# SATA_Ports.net
KiCad netlist of a schematic drawn in Altium Designer
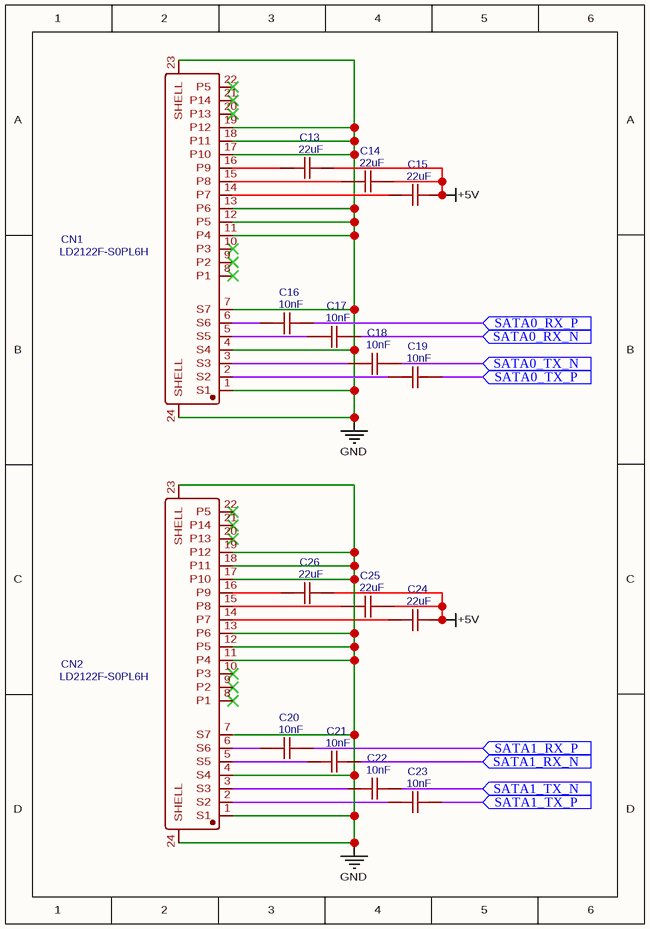
[diagram p0: SATA Ports.schdoc]

(export (version "E")
  (design (tool "Eeschema 10.0.6"))
  (components
    (comp (ref "C13")
      (value "22uF")
      (fields
        (field (name "MANUFACTURER") "Chinocera(华瓷)")
        (field (name "MANUFACTURER PART") "HGC0603R5226M160NTHJ")
        (field (name "CONTRIBUTOR") "lcsc")
      )
      (libsource (lib "altium-import") (part "root_0_22uF_"))
    )
    (comp (ref "C14")
      (value "22uF")
      (fields
        (field (name "MANUFACTURER") "Chinocera(华瓷)")
        (field (name "MANUFACTURER PART") "HGC0603R5226M160NTHJ")
        (field (name "CONTRIBUTOR") "lcsc")
      )
      (libsource (lib "altium-import") (part "root_0_22uF_"))
    )
    (comp (ref "C15")
      (value "22uF")
      (fields
        (field (name "MANUFACTURER") "Chinocera(华瓷)")
        (field (name "MANUFACTURER PART") "HGC0603R5226M160NTHJ")
        (field (name "CONTRIBUTOR") "lcsc")
      )
      (libsource (lib "altium-import") (part "root_0_22uF_"))
    )
    (comp (ref "C16")
      (value "10nF")
      (fields
        (field (name "MANUFACTURER") "FOJAN(富捷)")
        (field (name "MANUFACTURER PART") "FCC0402B103K500AT")
        (field (name "CONTRIBUTOR") "lcsc")
      )
      (libsource (lib "altium-import") (part "root_0_10nF_"))
    )
    (comp (ref "C17")
      (value "10nF")
      (fields
        (field (name "MANUFACTURER") "FOJAN(富捷)")
        (field (name "MANUFACTURER PART") "FCC0402B103K500AT")
        (field (name "CONTRIBUTOR") "lcsc")
      )
      (libsource (lib "altium-import") (part "root_0_10nF_"))
    )
    (comp (ref "C18")
      (value "10nF")
      (fields
        (field (name "MANUFACTURER") "FOJAN(富捷)")
        (field (name "MANUFACTURER PART") "FCC0402B103K500AT")
        (field (name "CONTRIBUTOR") "lcsc")
      )
      (libsource (lib "altium-import") (part "root_0_10nF_"))
    )
    (comp (ref "C19")
      (value "10nF")
      (fields
        (field (name "MANUFACTURER") "FOJAN(富捷)")
        (field (name "MANUFACTURER PART") "FCC0402B103K500AT")
        (field (name "CONTRIBUTOR") "lcsc")
      )
      (libsource (lib "altium-import") (part "root_0_10nF_"))
    )
    (comp (ref "C20")
      (value "10nF")
      (fields
        (field (name "MANUFACTURER") "FOJAN(富捷)")
        (field (name "MANUFACTURER PART") "FCC0402B103K500AT")
        (field (name "CONTRIBUTOR") "lcsc")
      )
      (libsource (lib "altium-import") (part "root_0_10nF_"))
    )
    (comp (ref "C21")
      (value "10nF")
      (fields
        (field (name "MANUFACTURER") "FOJAN(富捷)")
        (field (name "MANUFACTURER PART") "FCC0402B103K500AT")
        (field (name "CONTRIBUTOR") "lcsc")
      )
      (libsource (lib "altium-import") (part "root_0_10nF_"))
    )
    (comp (ref "C22")
      (value "10nF")
      (fields
        (field (name "MANUFACTURER") "FOJAN(富捷)")
        (field (name "MANUFACTURER PART") "FCC0402B103K500AT")
        (field (name "CONTRIBUTOR") "lcsc")
      )
      (libsource (lib "altium-import") (part "root_0_10nF_"))
    )
    (comp (ref "C23")
      (value "10nF")
      (fields
        (field (name "MANUFACTURER") "FOJAN(富捷)")
        (field (name "MANUFACTURER PART") "FCC0402B103K500AT")
        (field (name "CONTRIBUTOR") "lcsc")
      )
      (libsource (lib "altium-import") (part "root_0_10nF_"))
    )
    (comp (ref "C24")
      (value "22uF")
      (fields
        (field (name "MANUFACTURER") "Chinocera(华瓷)")
        (field (name "MANUFACTURER PART") "HGC0603R5226M160NTHJ")
        (field (name "CONTRIBUTOR") "lcsc")
      )
      (libsource (lib "altium-import") (part "root_0_22uF_"))
    )
    (comp (ref "C25")
      (value "22uF")
      (fields
        (field (name "MANUFACTURER") "Chinocera(华瓷)")
        (field (name "MANUFACTURER PART") "HGC0603R5226M160NTHJ")
        (field (name "CONTRIBUTOR") "lcsc")
      )
      (libsource (lib "altium-import") (part "root_0_22uF_"))
    )
    (comp (ref "C26")
      (value "22uF")
      (fields
        (field (name "MANUFACTURER") "Chinocera(华瓷)")
        (field (name "MANUFACTURER PART") "HGC0603R5226M160NTHJ")
        (field (name "CONTRIBUTOR") "lcsc")
      )
      (libsource (lib "altium-import") (part "root_0_22uF_"))
    )
    (comp (ref "CN1")
      (value "LD2122F-S0PL6H")
      (fields (field (name "MANUFACTURER") "FOXCONN(富士康)") (field (name "CONTRIBUTOR") "LCSC"))
      (libsource (lib "altium-import") (part "root_2_LD2122F-S0PL6H_"))
    )
    (comp (ref "CN2")
      (value "LD2122F-S0PL6H")
      (fields (field (name "MANUFACTURER") "FOXCONN(富士康)") (field (name "CONTRIBUTOR") "LCSC"))
      (libsource (lib "altium-import") (part "root_2_LD2122F-S0PL6H_"))
    )
  )
  (nets
    (net (code "1") (name "+5V") (class "Default")
      (node (ref "C13") (pin "2") (pinfunction "2_2") (pintype "passive"))
      (node (ref "C14") (pin "2") (pinfunction "2_2") (pintype "passive"))
      (node (ref "C15") (pin "2") (pinfunction "2_2") (pintype "passive"))
      (node (ref "C24") (pin "2") (pinfunction "2_2") (pintype "passive"))
      (node (ref "C25") (pin "2") (pinfunction "2_2") (pintype "passive"))
      (node (ref "C26") (pin "2") (pinfunction "2_2") (pintype "passive"))
    )
    (net (code "2") (name "/SATA0_RX_N") (class "Default")
      (node (ref "C17") (pin "2") (pinfunction "2_2") (pintype "passive"))
    )
    (net (code "3") (name "/SATA0_RX_P") (class "Default")
      (node (ref "C16") (pin "2") (pinfunction "2_2") (pintype "passive"))
    )
    (net (code "4") (name "/SATA0_TX_N") (class "Default")
      (node (ref "C18") (pin "2") (pinfunction "2_2") (pintype "passive"))
    )
    (net (code "5") (name "/SATA0_TX_P") (class "Default")
      (node (ref "C19") (pin "2") (pinfunction "2_2") (pintype "passive"))
    )
    (net (code "6") (name "/SATA1_RX_N") (class "Default")
      (node (ref "C21") (pin "2") (pinfunction "2_2") (pintype "passive"))
    )
    (net (code "7") (name "/SATA1_RX_P") (class "Default")
      (node (ref "C20") (pin "2") (pinfunction "2_2") (pintype "passive"))
    )
    (net (code "8") (name "/SATA1_TX_N") (class "Default")
      (node (ref "C22") (pin "2") (pinfunction "2_2") (pintype "passive"))
    )
    (net (code "9") (name "/SATA1_TX_P") (class "Default")
      (node (ref "C23") (pin "2") (pinfunction "2_2") (pintype "passive"))
    )
    (net (code "10") (name "GND") (class "Default")
      (node (ref "CN1") (pin "1") (pinfunction "S1_1") (pintype "passive"))
      (node (ref "CN1") (pin "11") (pinfunction "P4_11") (pintype "passive"))
      (node (ref "CN1") (pin "12") (pinfunction "P5_12") (pintype "passive"))
      (node (ref "CN1") (pin "13") (pinfunction "P6_13") (pintype "passive"))
      (node (ref "CN1") (pin "17") (pinfunction "P10_17") (pintype "passive"))
      (node (ref "CN1") (pin "18") (pinfunction "P11_18") (pintype "passive"))
      (node (ref "CN1") (pin "19") (pinfunction "P12_19") (pintype "passive"))
      (node (ref "CN1") (pin "23") (pinfunction "SHELL_23") (pintype "passive"))
      (node (ref "CN1") (pin "24") (pinfunction "SHELL_24") (pintype "passive"))
      (node (ref "CN1") (pin "4") (pinfunction "S4_4") (pintype "passive"))
      (node (ref "CN1") (pin "7") (pinfunction "S7_7") (pintype "passive"))
      (node (ref "CN2") (pin "1") (pinfunction "S1_1") (pintype "passive"))
      (node (ref "CN2") (pin "11") (pinfunction "P4_11") (pintype "passive"))
      (node (ref "CN2") (pin "12") (pinfunction "P5_12") (pintype "passive"))
      (node (ref "CN2") (pin "13") (pinfunction "P6_13") (pintype "passive"))
      (node (ref "CN2") (pin "17") (pinfunction "P10_17") (pintype "passive"))
      (node (ref "CN2") (pin "18") (pinfunction "P11_18") (pintype "passive"))
      (node (ref "CN2") (pin "19") (pinfunction "P12_19") (pintype "passive"))
      (node (ref "CN2") (pin "23") (pinfunction "SHELL_23") (pintype "passive"))
      (node (ref "CN2") (pin "24") (pinfunction "SHELL_24") (pintype "passive"))
      (node (ref "CN2") (pin "4") (pinfunction "S4_4") (pintype "passive"))
      (node (ref "CN2") (pin "7") (pinfunction "S7_7") (pintype "passive"))
    )
    (net (code "11") (name "Net-(CN1-P7)") (class "Default")
      (node (ref "C15") (pin "1") (pinfunction "1_1") (pintype "passive"))
      (node (ref "CN1") (pin "14") (pinfunction "P7_14") (pintype "passive"))
    )
    (net (code "12") (name "Net-(CN1-P8)") (class "Default")
      (node (ref "C14") (pin "1") (pinfunction "1_1") (pintype "passive"))
      (node (ref "CN1") (pin "15") (pinfunction "P8_15") (pintype "passive"))
    )
    (net (code "13") (name "Net-(CN1-P9)") (class "Default")
      (node (ref "C13") (pin "1") (pinfunction "1_1") (pintype "passive"))
      (node (ref "CN1") (pin "16") (pinfunction "P9_16") (pintype "passive"))
    )
    (net (code "14") (name "Net-(CN1-S2)") (class "Default")
      (node (ref "C19") (pin "1") (pinfunction "1_1") (pintype "passive"))
      (node (ref "CN1") (pin "2") (pinfunction "S2_2") (pintype "passive"))
    )
    (net (code "15") (name "Net-(CN1-S3)") (class "Default")
      (node (ref "C18") (pin "1") (pinfunction "1_1") (pintype "passive"))
      (node (ref "CN1") (pin "3") (pinfunction "S3_3") (pintype "passive"))
    )
    (net (code "16") (name "Net-(CN1-S5)") (class "Default")
      (node (ref "C17") (pin "1") (pinfunction "1_1") (pintype "passive"))
      (node (ref "CN1") (pin "5") (pinfunction "S5_5") (pintype "passive"))
    )
    (net (code "17") (name "Net-(CN1-S6)") (class "Default")
      (node (ref "C16") (pin "1") (pinfunction "1_1") (pintype "passive"))
      (node (ref "CN1") (pin "6") (pinfunction "S6_6") (pintype "passive"))
    )
    (net (code "18") (name "Net-(CN2-P7)") (class "Default")
      (node (ref "C24") (pin "1") (pinfunction "1_1") (pintype "passive"))
      (node (ref "CN2") (pin "14") (pinfunction "P7_14") (pintype "passive"))
    )
    (net (code "19") (name "Net-(CN2-P8)") (class "Default")
      (node (ref "C25") (pin "1") (pinfunction "1_1") (pintype "passive"))
      (node (ref "CN2") (pin "15") (pinfunction "P8_15") (pintype "passive"))
    )
    (net (code "20") (name "Net-(CN2-P9)") (class "Default")
      (node (ref "C26") (pin "1") (pinfunction "1_1") (pintype "passive"))
      (node (ref "CN2") (pin "16") (pinfunction "P9_16") (pintype "passive"))
    )
    (net (code "21") (name "Net-(CN2-S2)") (class "Default")
      (node (ref "C23") (pin "1") (pinfunction "1_1") (pintype "passive"))
      (node (ref "CN2") (pin "2") (pinfunction "S2_2") (pintype "passive"))
    )
    (net (code "22") (name "Net-(CN2-S3)") (class "Default")
      (node (ref "C22") (pin "1") (pinfunction "1_1") (pintype "passive"))
      (node (ref "CN2") (pin "3") (pinfunction "S3_3") (pintype "passive"))
    )
    (net (code "23") (name "Net-(CN2-S5)") (class "Default")
      (node (ref "C21") (pin "1") (pinfunction "1_1") (pintype "passive"))
      (node (ref "CN2") (pin "5") (pinfunction "S5_5") (pintype "passive"))
    )
    (net (code "24") (name "Net-(CN2-S6)") (class "Default")
      (node (ref "C20") (pin "1") (pinfunction "1_1") (pintype "passive"))
      (node (ref "CN2") (pin "6") (pinfunction "S6_6") (pintype "passive"))
    )
    (net (code "25") (name "unconnected-(CN1-P1-Pad8)") (class "Default")
      (node (ref "CN1") (pin "8") (pinfunction "P1_8") (pintype "passive+no_connect"))
    )
    (net (code "26") (name "unconnected-(CN1-P2-Pad9)") (class "Default")
      (node (ref "CN1") (pin "9") (pinfunction "P2_9") (pintype "passive+no_connect"))
    )
    (net (code "27") (name "unconnected-(CN1-P3-Pad10)") (class "Default")
      (node (ref "CN1") (pin "10") (pinfunction "P3_10") (pintype "passive+no_connect"))
    )
    (net (code "28") (name "unconnected-(CN1-P5-Pad22)") (class "Default")
      (node (ref "CN1") (pin "22") (pinfunction "P5_22") (pintype "passive+no_connect"))
    )
    (net (code "29") (name "unconnected-(CN1-P13-Pad20)") (class "Default")
      (node (ref "CN1") (pin "20") (pinfunction "P13_20") (pintype "passive+no_connect"))
    )
    (net (code "30") (name "unconnected-(CN1-P14-Pad21)") (class "Default")
      (node (ref "CN1") (pin "21") (pinfunction "P14_21") (pintype "passive+no_connect"))
    )
    (net (code "31") (name "unconnected-(CN2-P1-Pad8)") (class "Default")
      (node (ref "CN2") (pin "8") (pinfunction "P1_8") (pintype "passive+no_connect"))
    )
    (net (code "32") (name "unconnected-(CN2-P2-Pad9)") (class "Default")
      (node (ref "CN2") (pin "9") (pinfunction "P2_9") (pintype "passive+no_connect"))
    )
    (net (code "33") (name "unconnected-(CN2-P3-Pad10)") (class "Default")
      (node (ref "CN2") (pin "10") (pinfunction "P3_10") (pintype "passive+no_connect"))
    )
    (net (code "34") (name "unconnected-(CN2-P5-Pad22)") (class "Default")
      (node (ref "CN2") (pin "22") (pinfunction "P5_22") (pintype "passive+no_connect"))
    )
    (net (code "35") (name "unconnected-(CN2-P13-Pad20)") (class "Default")
      (node (ref "CN2") (pin "20") (pinfunction "P13_20") (pintype "passive+no_connect"))
    )
    (net (code "36") (name "unconnected-(CN2-P14-Pad21)") (class "Default")
      (node (ref "CN2") (pin "21") (pinfunction "P14_21") (pintype "passive+no_connect"))
    )
  )
)
